# uno_shield.net
KiCad netlist of a schematic drawn in EAGLE
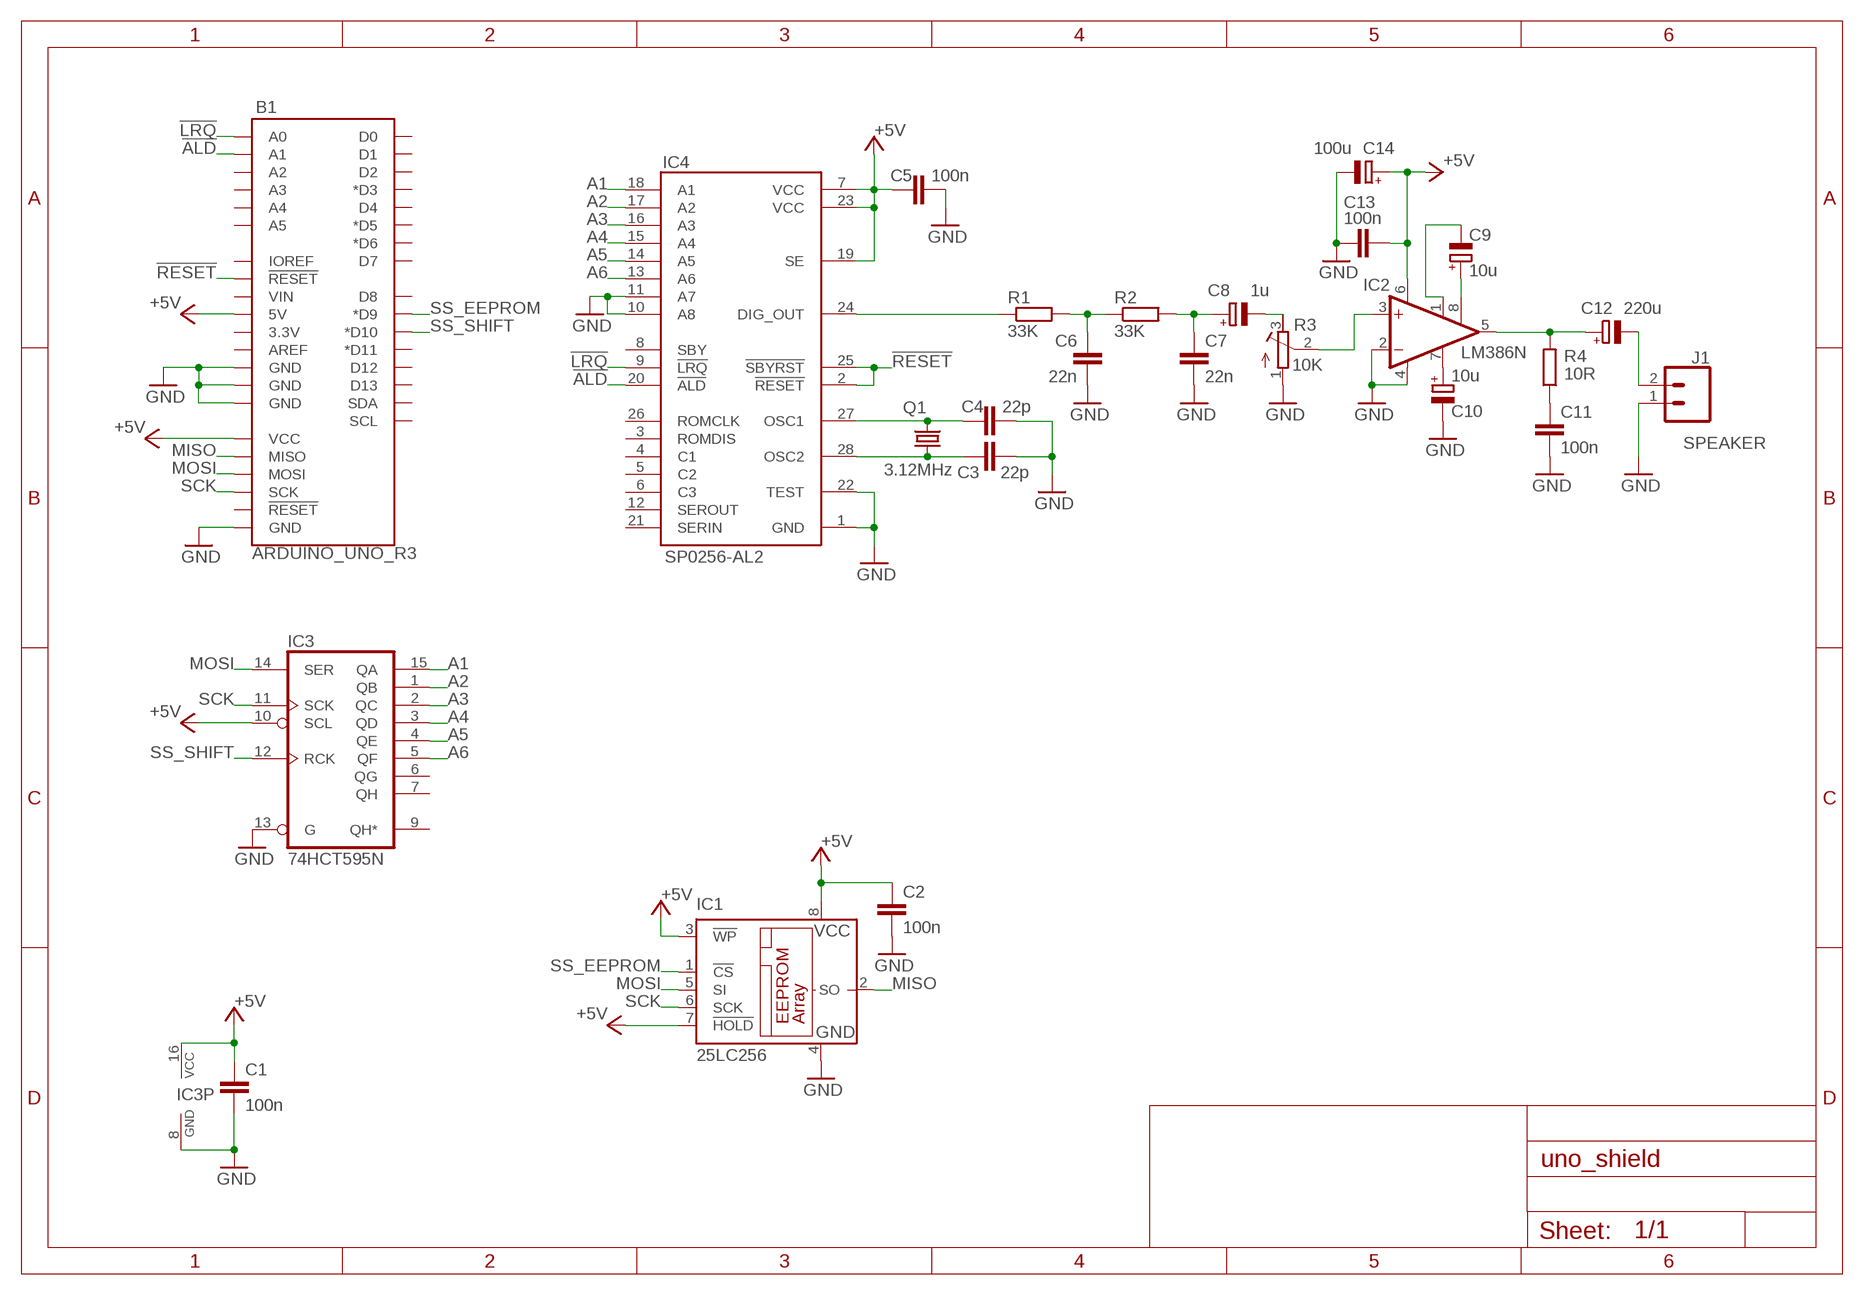
[diagram p0: schematic, sheet 1]

(export (version "E")
  (design (tool "Eeschema 10.0.6"))
  (components
    (comp (ref "B1")
      (value "ARDUINO_UNO_R3")
      (footprint "eagle-import:ARDUINO_R3")
      (libsource (lib "eagle-import") (part "ARDUINO_UNO_R3"))
    )
    (comp (ref "C1")
      (value "100n")
      (footprint "eagle-import:C025-024X044")
      (libsource (lib "eagle-import") (part "C-EU025-024X044"))
    )
    (comp (ref "C2")
      (value "100n")
      (footprint "eagle-import:C025-024X044")
      (libsource (lib "eagle-import") (part "C-EU025-024X044"))
    )
    (comp (ref "C3")
      (value "22p")
      (footprint "eagle-import:C025-024X044")
      (libsource (lib "eagle-import") (part "C-EU025-024X044"))
    )
    (comp (ref "C4")
      (value "22p")
      (footprint "eagle-import:C025-024X044")
      (libsource (lib "eagle-import") (part "C-EU025-024X044"))
    )
    (comp (ref "C5")
      (value "100n")
      (footprint "eagle-import:C025-024X044")
      (libsource (lib "eagle-import") (part "C-EU025-024X044"))
    )
    (comp (ref "C6")
      (value "22n")
      (footprint "eagle-import:C025-024X044")
      (libsource (lib "eagle-import") (part "C-EU025-024X044"))
    )
    (comp (ref "C7")
      (value "22n")
      (footprint "eagle-import:C025-024X044")
      (libsource (lib "eagle-import") (part "C-EU025-024X044"))
    )
    (comp (ref "C8")
      (value "1u")
      (footprint "eagle-import:E2,5-7")
      (libsource (lib "eagle-import") (part "CPOL-EUE2.5-7"))
    )
    (comp (ref "C9")
      (value "10u")
      (footprint "eagle-import:E2,5-5")
      (libsource (lib "eagle-import") (part "CPOL-EUE2.5-5"))
    )
    (comp (ref "C10")
      (value "10u")
      (footprint "eagle-import:E2,5-5")
      (libsource (lib "eagle-import") (part "CPOL-EUE2.5-5"))
    )
    (comp (ref "C11")
      (value "100n")
      (footprint "eagle-import:C025-024X044")
      (libsource (lib "eagle-import") (part "C-EU025-024X044"))
    )
    (comp (ref "C12")
      (value "220u")
      (footprint "eagle-import:E2,5-7")
      (libsource (lib "eagle-import") (part "CPOL-EUE2.5-7"))
    )
    (comp (ref "C13")
      (value "100n")
      (footprint "eagle-import:C025-024X044")
      (libsource (lib "eagle-import") (part "C-EU025-024X044"))
    )
    (comp (ref "C14")
      (value "100u")
      (footprint "eagle-import:E2,5-7")
      (libsource (lib "eagle-import") (part "CPOL-EUE2.5-7"))
    )
    (comp (ref "IC1")
      (value "25LC256")
      (footprint "eagle-import:DIL8")
      (fields (field (name "MF") "MICROCHIP") (field (name "MPN") "25LC080/P"))
      (libsource (lib "eagle-import") (part "25PLC080"))
    )
    (comp (ref "IC2")
      (value "LM386N")
      (footprint "eagle-import:DIL08")
      (libsource (lib "eagle-import") (part "LM386?-N1"))
    )
    (comp (ref "IC3")
      (value "74HCT595N")
      (footprint "eagle-import:DIL16")
      (libsource (lib "eagle-import") (part "74595NHCT"))
    )
    (comp (ref "IC4")
      (value "SP0256-AL2")
      (footprint "eagle-import:DIL28-6-OCT_PADS")
      (libsource (lib "eagle-import") (part "SP0256-AL2"))
    )
    (comp (ref "J1")
      (value "CONN_025MM")
      (footprint "eagle-import:SCREWTERMINAL-5MM-2")
      (libsource (lib "eagle-import") (part "CONN_025MM"))
    )
    (comp (ref "Q1")
      (value "3.12MHz")
      (footprint "eagle-import:HC49_S")
      (libsource (lib "eagle-import") (part "CRYSTALHC49S"))
    )
    (comp (ref "R1")
      (value "33K")
      (footprint "eagle-import:0309_10")
      (libsource (lib "eagle-import") (part "R-EU_0309/10"))
    )
    (comp (ref "R2")
      (value "33K")
      (footprint "eagle-import:0309_10")
      (libsource (lib "eagle-import") (part "R-EU_0309/10"))
    )
    (comp (ref "R3")
      (value "10K")
      (footprint "eagle-import:RTRIM3296W")
      (libsource (lib "eagle-import") (part "R-TRIMM3296W"))
    )
    (comp (ref "R4")
      (value "10R")
      (footprint "eagle-import:0309_10")
      (libsource (lib "eagle-import") (part "R-EU_0309/10"))
    )
  )
  (nets
    (net (code "1") (name "+5V") (class "Default")
      (node (ref "B1") (pin "5V") (pinfunction "5V_5V") (pintype "bidirectional"))
      (node (ref "B1") (pin "VCC") (pinfunction "VCC_VCC") (pintype "bidirectional"))
      (node (ref "C1") (pin "1") (pinfunction "1_1") (pintype "passive"))
      (node (ref "C13") (pin "2") (pinfunction "2_2") (pintype "passive"))
      (node (ref "C14") (pin "+") (pinfunction "+_+") (pintype "passive"))
      (node (ref "C2") (pin "1") (pinfunction "1_1") (pintype "passive"))
      (node (ref "C5") (pin "1") (pinfunction "1_1") (pintype "passive"))
      (node (ref "IC1") (pin "3") (pinfunction "~{WP}_3") (pintype "input"))
      (node (ref "IC1") (pin "7") (pinfunction "~{HOLD}_7") (pintype "input"))
      (node (ref "IC1") (pin "8") (pinfunction "VCC_8") (pintype "power_in"))
      (node (ref "IC2") (pin "6") (pinfunction "VS_6") (pintype "power_in"))
      (node (ref "IC3") (pin "10") (pinfunction "SCL_10") (pintype "input"))
      (node (ref "IC3") (pin "16") (pinfunction "VCC_16") (pintype "power_in"))
      (node (ref "IC4") (pin "19") (pinfunction "SE_19") (pintype "input"))
      (node (ref "IC4") (pin "23") (pinfunction "VCC_23") (pintype "power_in"))
      (node (ref "IC4") (pin "7") (pinfunction "VCC_7") (pintype "power_in"))
    )
    (net (code "2") (name "/A1") (class "Default")
      (node (ref "IC3") (pin "15") (pinfunction "QA_15") (pintype "tri_state"))
      (node (ref "IC4") (pin "18") (pinfunction "A1_18") (pintype "input"))
    )
    (net (code "3") (name "/A2") (class "Default")
      (node (ref "IC3") (pin "1") (pinfunction "QB_1") (pintype "tri_state"))
      (node (ref "IC4") (pin "17") (pinfunction "A2_17") (pintype "input"))
    )
    (net (code "4") (name "/A3") (class "Default")
      (node (ref "IC3") (pin "2") (pinfunction "QC_2") (pintype "tri_state"))
      (node (ref "IC4") (pin "16") (pinfunction "A3_16") (pintype "input"))
    )
    (net (code "5") (name "/A4") (class "Default")
      (node (ref "IC3") (pin "3") (pinfunction "QD_3") (pintype "tri_state"))
      (node (ref "IC4") (pin "15") (pinfunction "A4_15") (pintype "input"))
    )
    (net (code "6") (name "/A5") (class "Default")
      (node (ref "IC3") (pin "4") (pinfunction "QE_4") (pintype "tri_state"))
      (node (ref "IC4") (pin "14") (pinfunction "A5_14") (pintype "input"))
    )
    (net (code "7") (name "/A6") (class "Default")
      (node (ref "IC3") (pin "5") (pinfunction "QF_5") (pintype "tri_state"))
      (node (ref "IC4") (pin "13") (pinfunction "A6_13") (pintype "input"))
    )
    (net (code "8") (name "/MISO") (class "Default")
      (node (ref "B1") (pin "MISO") (pinfunction "MISO_MISO") (pintype "bidirectional"))
      (node (ref "IC1") (pin "2") (pinfunction "SO_2") (pintype "bidirectional"))
    )
    (net (code "9") (name "/MOSI") (class "Default")
      (node (ref "B1") (pin "MOSI") (pinfunction "MOSI_MOSI") (pintype "bidirectional"))
      (node (ref "IC1") (pin "5") (pinfunction "SI_5") (pintype "input"))
      (node (ref "IC3") (pin "14") (pinfunction "SER_14") (pintype "input"))
    )
    (net (code "10") (name "/SCK") (class "Default")
      (node (ref "B1") (pin "SCK") (pinfunction "SCK_SCK") (pintype "bidirectional"))
      (node (ref "IC1") (pin "6") (pinfunction "SCK_6") (pintype "input"))
      (node (ref "IC3") (pin "11") (pinfunction "SCK_11") (pintype "input"))
    )
    (net (code "11") (name "/SS_EEPROM") (class "Default")
      (node (ref "B1") (pin "D9") (pinfunction "*D9_D9") (pintype "bidirectional"))
      (node (ref "IC1") (pin "1") (pinfunction "~{CS}_1") (pintype "input"))
    )
    (net (code "12") (name "/SS_SHIFT") (class "Default")
      (node (ref "B1") (pin "D10") (pinfunction "*D10_D10") (pintype "bidirectional"))
      (node (ref "IC3") (pin "12") (pinfunction "RCK_12") (pintype "input"))
    )
    (net (code "13") (name "/~{ALD}") (class "Default")
      (node (ref "B1") (pin "A1") (pinfunction "A1_A1") (pintype "bidirectional"))
      (node (ref "IC4") (pin "20") (pinfunction "~{ALD}_20") (pintype "input"))
    )
    (net (code "14") (name "/~{LRQ}") (class "Default")
      (node (ref "B1") (pin "A0") (pinfunction "A0_A0") (pintype "bidirectional"))
      (node (ref "IC4") (pin "9") (pinfunction "~{LRQ}_9") (pintype "output"))
    )
    (net (code "15") (name "/~{RESET}") (class "Default")
      (node (ref "B1") (pin "RESET@1") (pinfunction "~{RESET}_RESET@1") (pintype "bidirectional"))
      (node (ref "IC4") (pin "2") (pinfunction "~{RESET}_2") (pintype "input"))
      (node (ref "IC4") (pin "25") (pinfunction "~{SBYRST}_25") (pintype "input"))
    )
    (net (code "16") (name "GND") (class "Default")
      (node (ref "B1") (pin "GND@1") (pinfunction "GND_GND@1") (pintype "bidirectional"))
      (node (ref "B1") (pin "GND@2") (pinfunction "GND_GND@2") (pintype "bidirectional"))
      (node (ref "B1") (pin "GND@3") (pinfunction "GND_GND@3") (pintype "bidirectional"))
      (node (ref "B1") (pin "GND@4") (pinfunction "GND_GND@4") (pintype "bidirectional"))
      (node (ref "C1") (pin "2") (pinfunction "2_2") (pintype "passive"))
      (node (ref "C10") (pin "-") (pinfunction "-_-") (pintype "passive"))
      (node (ref "C11") (pin "2") (pinfunction "2_2") (pintype "passive"))
      (node (ref "C13") (pin "1") (pinfunction "1_1") (pintype "passive"))
      (node (ref "C14") (pin "-") (pinfunction "-_-") (pintype "passive"))
      (node (ref "C2") (pin "2") (pinfunction "2_2") (pintype "passive"))
      (node (ref "C3") (pin "2") (pinfunction "2_2") (pintype "passive"))
      (node (ref "C4") (pin "2") (pinfunction "2_2") (pintype "passive"))
      (node (ref "C5") (pin "2") (pinfunction "2_2") (pintype "passive"))
      (node (ref "C6") (pin "2") (pinfunction "2_2") (pintype "passive"))
      (node (ref "C7") (pin "2") (pinfunction "2_2") (pintype "passive"))
      (node (ref "IC1") (pin "4") (pinfunction "GND_4") (pintype "power_in"))
      (node (ref "IC2") (pin "2") (pinfunction "-IN_2") (pintype "input"))
      (node (ref "IC2") (pin "4") (pinfunction "GND_4") (pintype "power_in"))
      (node (ref "IC3") (pin "13") (pinfunction "G_13") (pintype "input"))
      (node (ref "IC3") (pin "8") (pinfunction "GND_8") (pintype "power_in"))
      (node (ref "IC4") (pin "1") (pinfunction "GND_1") (pintype "power_in"))
      (node (ref "IC4") (pin "10") (pinfunction "A8_10") (pintype "input"))
      (node (ref "IC4") (pin "11") (pinfunction "A7_11") (pintype "input"))
      (node (ref "IC4") (pin "22") (pinfunction "TEST_22") (pintype "input"))
      (node (ref "J1") (pin "1") (pinfunction "1_1") (pintype "passive"))
      (node (ref "R3") (pin "1") (pinfunction "A_1") (pintype "passive"))
    )
    (net (code "17") (name "Net-(C6-Pad1)") (class "Default")
      (node (ref "C6") (pin "1") (pinfunction "1_1") (pintype "passive"))
      (node (ref "R1") (pin "2") (pinfunction "2_2") (pintype "passive"))
      (node (ref "R2") (pin "1") (pinfunction "1_1") (pintype "passive"))
    )
    (net (code "18") (name "Net-(C7-Pad1)") (class "Default")
      (node (ref "C7") (pin "1") (pinfunction "1_1") (pintype "passive"))
      (node (ref "C8") (pin "+") (pinfunction "+_+") (pintype "passive"))
      (node (ref "R2") (pin "2") (pinfunction "2_2") (pintype "passive"))
    )
    (net (code "19") (name "Net-(C9-Pad+)") (class "Default")
      (node (ref "C9") (pin "+") (pinfunction "+_+") (pintype "passive"))
      (node (ref "IC2") (pin "8") (pinfunction "GAIN_8") (pintype "passive"))
    )
    (net (code "20") (name "Net-(C9-Pad-)") (class "Default")
      (node (ref "C9") (pin "-") (pinfunction "-_-") (pintype "passive"))
      (node (ref "IC2") (pin "1") (pinfunction "GAIN_1") (pintype "passive"))
    )
    (net (code "21") (name "Net-(C11-Pad1)") (class "Default")
      (node (ref "C11") (pin "1") (pinfunction "1_1") (pintype "passive"))
      (node (ref "R4") (pin "1") (pinfunction "1_1") (pintype "passive"))
    )
    (net (code "22") (name "Net-(C12-Pad-)") (class "Default")
      (node (ref "C12") (pin "-") (pinfunction "-_-") (pintype "passive"))
      (node (ref "J1") (pin "2") (pinfunction "2_2") (pintype "passive"))
    )
    (net (code "23") (name "Net-(IC2-+IN)") (class "Default")
      (node (ref "IC2") (pin "3") (pinfunction "+IN_3") (pintype "input"))
      (node (ref "R3") (pin "2") (pinfunction "S_2") (pintype "passive"))
    )
    (net (code "24") (name "Net-(IC2-BYPASS)") (class "Default")
      (node (ref "C10") (pin "+") (pinfunction "+_+") (pintype "passive"))
      (node (ref "IC2") (pin "7") (pinfunction "BYPASS_7") (pintype "passive"))
    )
    (net (code "25") (name "Net-(IC2-OUT)") (class "Default")
      (node (ref "C12") (pin "+") (pinfunction "+_+") (pintype "passive"))
      (node (ref "IC2") (pin "5") (pinfunction "OUT_5") (pintype "output"))
      (node (ref "R4") (pin "2") (pinfunction "2_2") (pintype "passive"))
    )
    (net (code "26") (name "Net-(IC4-DIG_OUT)") (class "Default")
      (node (ref "IC4") (pin "24") (pinfunction "DIG_OUT_24") (pintype "output"))
      (node (ref "R1") (pin "1") (pinfunction "1_1") (pintype "passive"))
    )
    (net (code "27") (name "Net-(IC4-OSC1)") (class "Default")
      (node (ref "C4") (pin "1") (pinfunction "1_1") (pintype "passive"))
      (node (ref "IC4") (pin "27") (pinfunction "OSC1_27") (pintype "input"))
      (node (ref "Q1") (pin "2") (pinfunction "2_2") (pintype "passive"))
    )
    (net (code "28") (name "Net-(IC4-OSC2)") (class "Default")
      (node (ref "C3") (pin "1") (pinfunction "1_1") (pintype "passive"))
      (node (ref "IC4") (pin "28") (pinfunction "OSC2_28") (pintype "output"))
      (node (ref "Q1") (pin "1") (pinfunction "1_1") (pintype "passive"))
    )
    (net (code "29") (name "Net-(R3-E)") (class "Default")
      (node (ref "C8") (pin "-") (pinfunction "-_-") (pintype "passive"))
      (node (ref "R3") (pin "3") (pinfunction "E_3") (pintype "passive"))
    )
    (net (code "30") (name "unconnected-(B1-*D3-PadD3)") (class "Default")
      (node (ref "B1") (pin "D3") (pinfunction "*D3_D3") (pintype "bidirectional"))
    )
    (net (code "31") (name "unconnected-(B1-*D5-PadD5)") (class "Default")
      (node (ref "B1") (pin "D5") (pinfunction "*D5_D5") (pintype "bidirectional"))
    )
    (net (code "32") (name "unconnected-(B1-*D6-PadD6)") (class "Default")
      (node (ref "B1") (pin "D6") (pinfunction "*D6_D6") (pintype "bidirectional"))
    )
    (net (code "33") (name "unconnected-(B1-*D11-PadD11)") (class "Default")
      (node (ref "B1") (pin "D11") (pinfunction "*D11_D11") (pintype "bidirectional"))
    )
    (net (code "34") (name "unconnected-(B1-Pad3.3V)") (class "Default")
      (node (ref "B1") (pin "3.3V") (pinfunction "3.3V_3.3V") (pintype "bidirectional"))
    )
    (net (code "35") (name "unconnected-(B1-PadA2)") (class "Default")
      (node (ref "B1") (pin "A2") (pinfunction "A2_A2") (pintype "bidirectional"))
    )
    (net (code "36") (name "unconnected-(B1-PadA3)") (class "Default")
      (node (ref "B1") (pin "A3") (pinfunction "A3_A3") (pintype "bidirectional"))
    )
    (net (code "37") (name "unconnected-(B1-PadA4)") (class "Default")
      (node (ref "B1") (pin "A4") (pinfunction "A4_A4") (pintype "bidirectional"))
    )
    (net (code "38") (name "unconnected-(B1-PadA5)") (class "Default")
      (node (ref "B1") (pin "A5") (pinfunction "A5_A5") (pintype "bidirectional"))
    )
    (net (code "39") (name "unconnected-(B1-PadAREF)") (class "Default")
      (node (ref "B1") (pin "AREF") (pinfunction "AREF_AREF") (pintype "bidirectional"))
    )
    (net (code "40") (name "unconnected-(B1-PadD0)") (class "Default")
      (node (ref "B1") (pin "D0") (pinfunction "D0_D0") (pintype "bidirectional"))
    )
    (net (code "41") (name "unconnected-(B1-PadD1)") (class "Default")
      (node (ref "B1") (pin "D1") (pinfunction "D1_D1") (pintype "bidirectional"))
    )
    (net (code "42") (name "unconnected-(B1-PadD2)") (class "Default")
      (node (ref "B1") (pin "D2") (pinfunction "D2_D2") (pintype "bidirectional"))
    )
    (net (code "43") (name "unconnected-(B1-PadD4)") (class "Default")
      (node (ref "B1") (pin "D4") (pinfunction "D4_D4") (pintype "bidirectional"))
    )
    (net (code "44") (name "unconnected-(B1-PadD7)") (class "Default")
      (node (ref "B1") (pin "D7") (pinfunction "D7_D7") (pintype "bidirectional"))
    )
    (net (code "45") (name "unconnected-(B1-PadD8)") (class "Default")
      (node (ref "B1") (pin "D8") (pinfunction "D8_D8") (pintype "bidirectional"))
    )
    (net (code "46") (name "unconnected-(B1-PadD12)") (class "Default")
      (node (ref "B1") (pin "D12") (pinfunction "D12_D12") (pintype "bidirectional"))
    )
    (net (code "47") (name "unconnected-(B1-PadD13)") (class "Default")
      (node (ref "B1") (pin "D13") (pinfunction "D13_D13") (pintype "bidirectional"))
    )
    (net (code "48") (name "unconnected-(B1-PadIOREF)") (class "Default")
      (node (ref "B1") (pin "IOREF") (pinfunction "IOREF_IOREF") (pintype "bidirectional"))
    )
    (net (code "49") (name "unconnected-(B1-PadSCL)") (class "Default")
      (node (ref "B1") (pin "SCL") (pinfunction "SCL_SCL") (pintype "bidirectional"))
    )
    (net (code "50") (name "unconnected-(B1-PadSDA)") (class "Default")
      (node (ref "B1") (pin "SDA") (pinfunction "SDA_SDA") (pintype "bidirectional"))
    )
    (net (code "51") (name "unconnected-(B1-PadVIN)") (class "Default")
      (node (ref "B1") (pin "VIN") (pinfunction "VIN_VIN") (pintype "bidirectional"))
    )
    (net (code "52") (name "unconnected-(B1-~{RESET}-PadRESET@2)") (class "Default")
      (node (ref "B1") (pin "RESET@2") (pinfunction "~{RESET}_RESET@2") (pintype "bidirectional"))
    )
    (net (code "53") (name "unconnected-(IC3A-QG-Pad6)") (class "Default")
      (node (ref "IC3") (pin "6") (pinfunction "QG_6") (pintype "tri_state"))
    )
    (net (code "54") (name "unconnected-(IC3A-QH*-Pad9)") (class "Default")
      (node (ref "IC3") (pin "9") (pinfunction "QH*_9") (pintype "tri_state"))
    )
    (net (code "55") (name "unconnected-(IC3A-QH-Pad7)") (class "Default")
      (node (ref "IC3") (pin "7") (pinfunction "QH_7") (pintype "tri_state"))
    )
    (net (code "56") (name "unconnected-(IC4-C1-Pad4)") (class "Default")
      (node (ref "IC4") (pin "4") (pinfunction "C1_4") (pintype "output"))
    )
    (net (code "57") (name "unconnected-(IC4-C2-Pad5)") (class "Default")
      (node (ref "IC4") (pin "5") (pinfunction "C2_5") (pintype "output"))
    )
    (net (code "58") (name "unconnected-(IC4-C3-Pad6)") (class "Default")
      (node (ref "IC4") (pin "6") (pinfunction "C3_6") (pintype "output"))
    )
    (net (code "59") (name "unconnected-(IC4-ROMCLK-Pad26)") (class "Default")
      (node (ref "IC4") (pin "26") (pinfunction "ROMCLK_26") (pintype "output"))
    )
    (net (code "60") (name "unconnected-(IC4-ROMDIS-Pad3)") (class "Default")
      (node (ref "IC4") (pin "3") (pinfunction "ROMDIS_3") (pintype "output"))
    )
    (net (code "61") (name "unconnected-(IC4-SBY-Pad8)") (class "Default")
      (node (ref "IC4") (pin "8") (pinfunction "SBY_8") (pintype "output"))
    )
    (net (code "62") (name "unconnected-(IC4-SERIN-Pad21)") (class "Default")
      (node (ref "IC4") (pin "21") (pinfunction "SERIN_21") (pintype "input"))
    )
    (net (code "63") (name "unconnected-(IC4-SEROUT-Pad12)") (class "Default")
      (node (ref "IC4") (pin "12") (pinfunction "SEROUT_12") (pintype "output"))
    )
  )
)
